# traffic_light.net
KiCad netlist of a schematic drawn in EAGLE
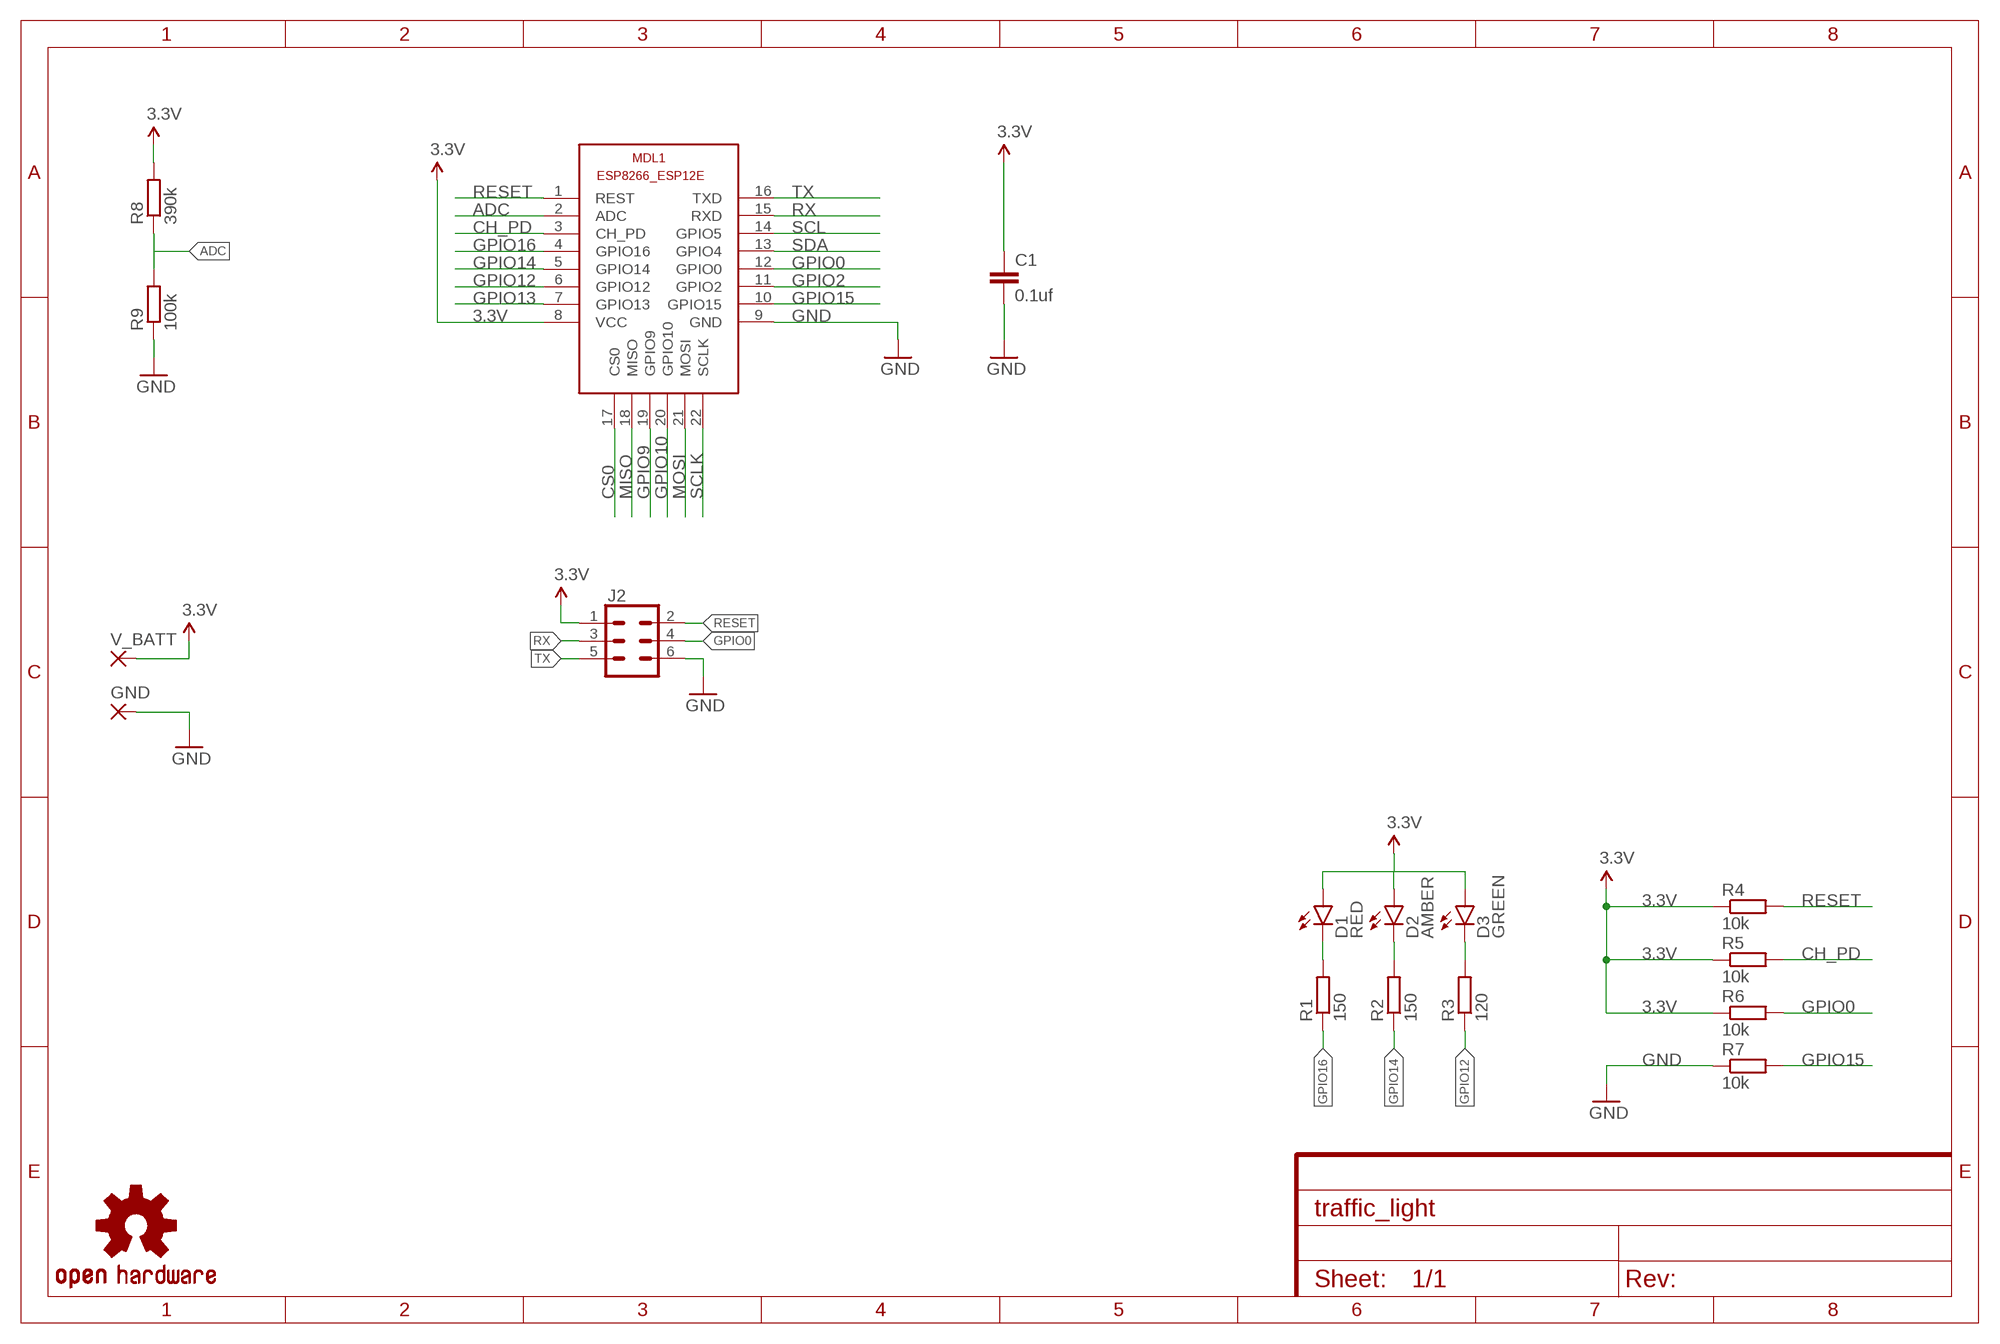
[diagram p0: schematic, sheet 1]

(export (version "E")
  (design (tool "Eeschema 10.0.6"))
  (components
    (comp (ref "C1")
      (value "0.1uf")
      (footprint "eagle-import:C0805")
      (libsource (lib "eagle-import") (part "C-EUC0805"))
    )
    (comp (ref "D1")
      (value "RED")
      (footprint "eagle-import:LED-0603")
      (libsource (lib "eagle-import") (part "LED0603"))
    )
    (comp (ref "D2")
      (value "AMBER")
      (footprint "eagle-import:LED-0603")
      (libsource (lib "eagle-import") (part "LED0603"))
    )
    (comp (ref "D3")
      (value "GREEN")
      (footprint "eagle-import:LED-0603")
      (libsource (lib "eagle-import") (part "LED0603"))
    )
    (comp (ref "GND")
      (value "SMD5")
      (footprint "eagle-import:SMD2,54-5,08")
      (libsource (lib "eagle-import") (part "SMD5"))
    )
    (comp (ref "J2")
      (value "CONN_03X2SHROUD")
      (footprint "eagle-import:2X3-SHROUDED")
      (libsource (lib "eagle-import") (part "CONN_03X2SHROUD"))
    )
    (comp (ref "LOGO1")
      (value "OSHW-LOGOS")
      (footprint "eagle-import:OSHW-LOGO-S")
      (libsource (lib "eagle-import") (part "OSHW-LOGOS"))
    )
    (comp (ref "MDL1")
      (value "ESP8266-12EESP8266-ESP12E")
      (footprint "eagle-import:ESP8266-ESP12E")
      (libsource (lib "eagle-import") (part "ESP8266-12EESP8266-ESP12E"))
    )
    (comp (ref "R1")
      (value "150")
      (footprint "eagle-import:R0805")
      (libsource (lib "eagle-import") (part "R-EU_R0805"))
    )
    (comp (ref "R2")
      (value "150")
      (footprint "eagle-import:R0805")
      (libsource (lib "eagle-import") (part "R-EU_R0805"))
    )
    (comp (ref "R3")
      (value "120")
      (footprint "eagle-import:R0805")
      (libsource (lib "eagle-import") (part "R-EU_R0805"))
    )
    (comp (ref "R4")
      (value "10k")
      (footprint "eagle-import:R0805")
      (libsource (lib "eagle-import") (part "R-EU_R0805"))
    )
    (comp (ref "R5")
      (value "10k")
      (footprint "eagle-import:R0805")
      (libsource (lib "eagle-import") (part "R-EU_R0805"))
    )
    (comp (ref "R6")
      (value "10k")
      (footprint "eagle-import:R0805")
      (libsource (lib "eagle-import") (part "R-EU_R0805"))
    )
    (comp (ref "R7")
      (value "10k")
      (footprint "eagle-import:R0805")
      (libsource (lib "eagle-import") (part "R-EU_R0805"))
    )
    (comp (ref "R8")
      (value "390k")
      (footprint "eagle-import:R0805")
      (libsource (lib "eagle-import") (part "R-EU_R0805"))
    )
    (comp (ref "R9")
      (value "100k")
      (footprint "eagle-import:R0805")
      (libsource (lib "eagle-import") (part "R-EU_R0805"))
    )
    (comp (ref "V_BATT")
      (value "SMD5")
      (footprint "eagle-import:SMD2,54-5,08")
      (libsource (lib "eagle-import") (part "SMD5"))
    )
  )
  (nets
    (net (code "1") (name "/CH_PD") (class "Default")
      (node (ref "MDL1") (pin "3") (pinfunction "CH_PD_3") (pintype "bidirectional"))
      (node (ref "R5") (pin "2") (pinfunction "2_2") (pintype "passive"))
    )
    (net (code "2") (name "/CS0") (class "Default")
      (node (ref "MDL1") (pin "17") (pinfunction "CS0_17") (pintype "bidirectional"))
    )
    (net (code "3") (name "/GPIO2") (class "Default")
      (node (ref "MDL1") (pin "11") (pinfunction "GPIO2_11") (pintype "bidirectional"))
    )
    (net (code "4") (name "/GPIO9") (class "Default")
      (node (ref "MDL1") (pin "19") (pinfunction "GPIO9_19") (pintype "bidirectional"))
    )
    (net (code "5") (name "/GPIO10") (class "Default")
      (node (ref "MDL1") (pin "20") (pinfunction "GPIO10_20") (pintype "bidirectional"))
    )
    (net (code "6") (name "/GPIO13") (class "Default")
      (node (ref "MDL1") (pin "7") (pinfunction "GPIO13_7") (pintype "bidirectional"))
    )
    (net (code "7") (name "/GPIO15") (class "Default")
      (node (ref "MDL1") (pin "10") (pinfunction "GPIO15_10") (pintype "bidirectional"))
      (node (ref "R7") (pin "2") (pinfunction "2_2") (pintype "passive"))
    )
    (net (code "8") (name "/MISO") (class "Default")
      (node (ref "MDL1") (pin "18") (pinfunction "MISO_18") (pintype "bidirectional"))
    )
    (net (code "9") (name "/MOSI") (class "Default")
      (node (ref "MDL1") (pin "21") (pinfunction "MOSI_21") (pintype "bidirectional"))
    )
    (net (code "10") (name "/SCL") (class "Default")
      (node (ref "MDL1") (pin "14") (pinfunction "GPIO5_14") (pintype "bidirectional"))
    )
    (net (code "11") (name "/SCLK") (class "Default")
      (node (ref "MDL1") (pin "22") (pinfunction "SCLK_22") (pintype "bidirectional"))
    )
    (net (code "12") (name "/SDA") (class "Default")
      (node (ref "MDL1") (pin "13") (pinfunction "GPIO4_13") (pintype "bidirectional"))
    )
    (net (code "13") (name "3.3V") (class "Default")
      (node (ref "C1") (pin "1") (pinfunction "1_1") (pintype "passive"))
      (node (ref "D1") (pin "A") (pinfunction "A_A") (pintype "passive"))
      (node (ref "D2") (pin "A") (pinfunction "A_A") (pintype "passive"))
      (node (ref "D3") (pin "A") (pinfunction "A_A") (pintype "passive"))
      (node (ref "J2") (pin "1") (pinfunction "1_1") (pintype "bidirectional"))
      (node (ref "MDL1") (pin "8") (pinfunction "VCC_8") (pintype "bidirectional"))
      (node (ref "R4") (pin "1") (pinfunction "1_1") (pintype "passive"))
      (node (ref "R5") (pin "1") (pinfunction "1_1") (pintype "passive"))
      (node (ref "R6") (pin "1") (pinfunction "1_1") (pintype "passive"))
      (node (ref "R8") (pin "2") (pinfunction "2_2") (pintype "passive"))
      (node (ref "V_BATT") (pin "1") (pinfunction "P_1") (pintype "passive"))
    )
    (net (code "14") (name "ADC") (class "Default")
      (node (ref "MDL1") (pin "2") (pinfunction "ADC_2") (pintype "bidirectional"))
      (node (ref "R8") (pin "1") (pinfunction "1_1") (pintype "passive"))
      (node (ref "R9") (pin "2") (pinfunction "2_2") (pintype "passive"))
    )
    (net (code "15") (name "GND") (class "Default")
      (node (ref "C1") (pin "2") (pinfunction "2_2") (pintype "passive"))
      (node (ref "GND") (pin "1") (pinfunction "P_1") (pintype "passive"))
      (node (ref "J2") (pin "6") (pinfunction "6_6") (pintype "bidirectional"))
      (node (ref "MDL1") (pin "9") (pinfunction "GND_9") (pintype "bidirectional"))
      (node (ref "R7") (pin "1") (pinfunction "1_1") (pintype "passive"))
      (node (ref "R9") (pin "1") (pinfunction "1_1") (pintype "passive"))
    )
    (net (code "16") (name "GPIO0") (class "Default")
      (node (ref "J2") (pin "4") (pinfunction "4_4") (pintype "bidirectional"))
      (node (ref "MDL1") (pin "12") (pinfunction "GPIO0_12") (pintype "bidirectional"))
      (node (ref "R6") (pin "2") (pinfunction "2_2") (pintype "passive"))
    )
    (net (code "17") (name "GPIO12") (class "Default")
      (node (ref "MDL1") (pin "6") (pinfunction "GPIO12_6") (pintype "bidirectional"))
      (node (ref "R3") (pin "1") (pinfunction "1_1") (pintype "passive"))
    )
    (net (code "18") (name "GPIO14") (class "Default")
      (node (ref "MDL1") (pin "5") (pinfunction "GPIO14_5") (pintype "bidirectional"))
      (node (ref "R2") (pin "1") (pinfunction "1_1") (pintype "passive"))
    )
    (net (code "19") (name "GPIO16") (class "Default")
      (node (ref "MDL1") (pin "4") (pinfunction "GPIO16_4") (pintype "bidirectional"))
      (node (ref "R1") (pin "1") (pinfunction "1_1") (pintype "passive"))
    )
    (net (code "20") (name "Net-(D1-PadC)") (class "Default")
      (node (ref "D1") (pin "C") (pinfunction "C_C") (pintype "passive"))
      (node (ref "R1") (pin "2") (pinfunction "2_2") (pintype "passive"))
    )
    (net (code "21") (name "Net-(D2-PadC)") (class "Default")
      (node (ref "D2") (pin "C") (pinfunction "C_C") (pintype "passive"))
      (node (ref "R2") (pin "2") (pinfunction "2_2") (pintype "passive"))
    )
    (net (code "22") (name "Net-(D3-PadC)") (class "Default")
      (node (ref "D3") (pin "C") (pinfunction "C_C") (pintype "passive"))
      (node (ref "R3") (pin "2") (pinfunction "2_2") (pintype "passive"))
    )
    (net (code "23") (name "RESET") (class "Default")
      (node (ref "J2") (pin "2") (pinfunction "2_2") (pintype "bidirectional"))
      (node (ref "MDL1") (pin "1") (pinfunction "REST_1") (pintype "bidirectional"))
      (node (ref "R4") (pin "2") (pinfunction "2_2") (pintype "passive"))
    )
    (net (code "24") (name "RX") (class "Default")
      (node (ref "J2") (pin "3") (pinfunction "3_3") (pintype "bidirectional"))
      (node (ref "MDL1") (pin "15") (pinfunction "RXD_15") (pintype "bidirectional"))
    )
    (net (code "25") (name "TX") (class "Default")
      (node (ref "J2") (pin "5") (pinfunction "5_5") (pintype "bidirectional"))
      (node (ref "MDL1") (pin "16") (pinfunction "TXD_16") (pintype "bidirectional"))
    )
  )
)
